# Adapter_LK-1.net
KiCad netlist of a schematic drawn in EAGLE
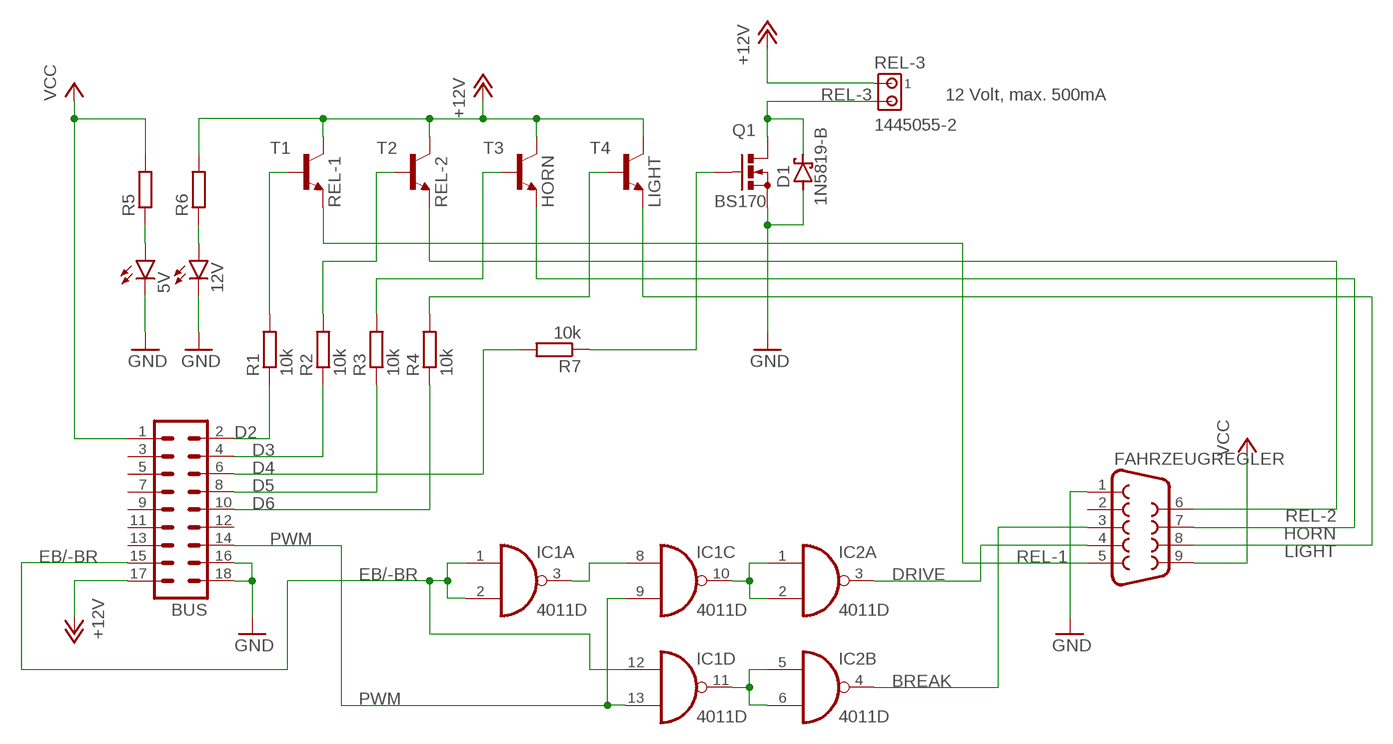
[diagram p0: schematic, sheet 1]

(export (version "E")
  (design (tool "Eeschema 10.0.6"))
  (components
    (comp (ref "5V")
      (value "LED3MM")
      (footprint "eagle-import:LED3MM")
      (libsource (lib "eagle-import") (part "LED3MM"))
    )
    (comp (ref "12V")
      (value "LED3MM")
      (footprint "eagle-import:LED3MM")
      (libsource (lib "eagle-import") (part "LED3MM"))
    )
    (comp (ref "BUS")
      (value "MA09-2")
      (footprint "eagle-import:MA09-2")
      (libsource (lib "eagle-import") (part "MA09-2"))
    )
    (comp (ref "D1")
      (value "1N5819-B")
      (footprint "eagle-import:DO41-7.6")
      (libsource (lib "eagle-import") (part "1N5819-B"))
    )
    (comp (ref "FAHRZEUGREGLER")
      (value "F09HP")
      (footprint "eagle-import:F09HP")
      (libsource (lib "eagle-import") (part "F09HP"))
    )
    (comp (ref "IC1")
      (value "4011D")
      (footprint "eagle-import:SO14")
      (libsource (lib "eagle-import") (part "4011D"))
    )
    (comp (ref "IC2")
      (value "4011D")
      (footprint "eagle-import:SO14")
      (libsource (lib "eagle-import") (part "4011D"))
    )
    (comp (ref "Q1")
      (value "BS170")
      (footprint "eagle-import:SOT54E")
      (libsource (lib "eagle-import") (part "BS170"))
    )
    (comp (ref "R1")
      (value "10k")
      (footprint "eagle-import:0204V")
      (libsource (lib "eagle-import") (part "R-EU_0204/2V"))
    )
    (comp (ref "R2")
      (value "10k")
      (footprint "eagle-import:0204V")
      (libsource (lib "eagle-import") (part "R-EU_0204/2V"))
    )
    (comp (ref "R3")
      (value "10k")
      (footprint "eagle-import:0204V")
      (libsource (lib "eagle-import") (part "R-EU_0204/2V"))
    )
    (comp (ref "R4")
      (value "10k")
      (footprint "eagle-import:0204V")
      (libsource (lib "eagle-import") (part "R-EU_0204/2V"))
    )
    (comp (ref "R5")
      (value "R-EU_0204/2V")
      (footprint "eagle-import:0204V")
      (libsource (lib "eagle-import") (part "R-EU_0204/2V"))
    )
    (comp (ref "R6")
      (value "R-EU_0204/2V")
      (footprint "eagle-import:0204V")
      (libsource (lib "eagle-import") (part "R-EU_0204/2V"))
    )
    (comp (ref "R7")
      (value "10k")
      (footprint "eagle-import:0204V")
      (libsource (lib "eagle-import") (part "R-EU_0204/2V"))
    )
    (comp (ref "REL-3")
      (value "1445055-2")
      (footprint "eagle-import:1445055-2")
      (libsource (lib "eagle-import") (part "1445055-2"))
    )
    (comp (ref "T1")
      (value "-NPN-TO92")
      (footprint "eagle-import:TO92")
      (libsource (lib "eagle-import") (part "-NPN-TO92"))
    )
    (comp (ref "T2")
      (value "-NPN-TO92")
      (footprint "eagle-import:TO92")
      (libsource (lib "eagle-import") (part "-NPN-TO92"))
    )
    (comp (ref "T3")
      (value "-NPN-TO92")
      (footprint "eagle-import:TO92")
      (libsource (lib "eagle-import") (part "-NPN-TO92"))
    )
    (comp (ref "T4")
      (value "-NPN-TO92")
      (footprint "eagle-import:TO92")
      (libsource (lib "eagle-import") (part "-NPN-TO92"))
    )
  )
  (nets
    (net (code "1") (name "+12V") (class "Default")
      (node (ref "BUS") (pin "17") (pinfunction "17_17") (pintype "passive"))
      (node (ref "R6") (pin "2") (pinfunction "2_2") (pintype "passive"))
      (node (ref "REL-3") (pin "1") (pinfunction "1_1") (pintype "passive"))
      (node (ref "T1") (pin "3") (pinfunction "C_3") (pintype "passive"))
      (node (ref "T2") (pin "3") (pinfunction "C_3") (pintype "passive"))
      (node (ref "T3") (pin "3") (pinfunction "C_3") (pintype "passive"))
      (node (ref "T4") (pin "3") (pinfunction "C_3") (pintype "passive"))
    )
    (net (code "2") (name "/BREAK") (class "Default")
      (node (ref "FAHRZEUGREGLER") (pin "3") (pinfunction "3_3") (pintype "passive"))
      (node (ref "IC2") (pin "4") (pinfunction "O_4") (pintype "output"))
    )
    (net (code "3") (name "/D2") (class "Default")
      (node (ref "BUS") (pin "2") (pinfunction "2_2") (pintype "passive"))
      (node (ref "R1") (pin "1") (pinfunction "1_1") (pintype "passive"))
    )
    (net (code "4") (name "/D3") (class "Default")
      (node (ref "BUS") (pin "4") (pinfunction "4_4") (pintype "passive"))
      (node (ref "R2") (pin "1") (pinfunction "1_1") (pintype "passive"))
    )
    (net (code "5") (name "/D4") (class "Default")
      (node (ref "BUS") (pin "6") (pinfunction "6_6") (pintype "passive"))
      (node (ref "R7") (pin "2") (pinfunction "2_2") (pintype "passive"))
    )
    (net (code "6") (name "/D5") (class "Default")
      (node (ref "BUS") (pin "8") (pinfunction "8_8") (pintype "passive"))
      (node (ref "R3") (pin "1") (pinfunction "1_1") (pintype "passive"))
    )
    (net (code "7") (name "/D6") (class "Default")
      (node (ref "BUS") (pin "10") (pinfunction "10_10") (pintype "passive"))
      (node (ref "R4") (pin "1") (pinfunction "1_1") (pintype "passive"))
    )
    (net (code "8") (name "/DRIVE") (class "Default")
      (node (ref "FAHRZEUGREGLER") (pin "4") (pinfunction "4_4") (pintype "passive"))
      (node (ref "IC2") (pin "3") (pinfunction "O_3") (pintype "output"))
    )
    (net (code "9") (name "/EB{slash}-BR") (class "Default")
      (node (ref "BUS") (pin "15") (pinfunction "15_15") (pintype "passive"))
      (node (ref "IC1") (pin "1") (pinfunction "I0_1") (pintype "input"))
      (node (ref "IC1") (pin "12") (pinfunction "I0_12") (pintype "input"))
      (node (ref "IC1") (pin "2") (pinfunction "I1_2") (pintype "input"))
    )
    (net (code "10") (name "/HORN") (class "Default")
      (node (ref "FAHRZEUGREGLER") (pin "7") (pinfunction "7_7") (pintype "passive"))
      (node (ref "T3") (pin "1") (pinfunction "E_1") (pintype "passive"))
    )
    (net (code "11") (name "/LIGHT") (class "Default")
      (node (ref "FAHRZEUGREGLER") (pin "8") (pinfunction "8_8") (pintype "passive"))
      (node (ref "T4") (pin "1") (pinfunction "E_1") (pintype "passive"))
    )
    (net (code "12") (name "/PWM") (class "Default")
      (node (ref "BUS") (pin "14") (pinfunction "14_14") (pintype "passive"))
      (node (ref "IC1") (pin "13") (pinfunction "I1_13") (pintype "input"))
      (node (ref "IC1") (pin "9") (pinfunction "I1_9") (pintype "input"))
    )
    (net (code "13") (name "/REL-1") (class "Default")
      (node (ref "FAHRZEUGREGLER") (pin "5") (pinfunction "5_5") (pintype "passive"))
      (node (ref "T1") (pin "1") (pinfunction "E_1") (pintype "passive"))
    )
    (net (code "14") (name "/REL-2") (class "Default")
      (node (ref "FAHRZEUGREGLER") (pin "6") (pinfunction "6_6") (pintype "passive"))
      (node (ref "T2") (pin "1") (pinfunction "E_1") (pintype "passive"))
    )
    (net (code "15") (name "/REL-3") (class "Default")
      (node (ref "D1") (pin "C") (pinfunction "C_C") (pintype "passive"))
      (node (ref "Q1") (pin "D") (pinfunction "D_D") (pintype "passive"))
      (node (ref "REL-3") (pin "2") (pinfunction "2_2") (pintype "passive"))
    )
    (net (code "16") (name "GND") (class "Default")
      (node (ref "12V") (pin "K") (pinfunction "C_K") (pintype "passive"))
      (node (ref "5V") (pin "K") (pinfunction "C_K") (pintype "passive"))
      (node (ref "BUS") (pin "16") (pinfunction "16_16") (pintype "passive"))
      (node (ref "BUS") (pin "18") (pinfunction "18_18") (pintype "passive"))
      (node (ref "D1") (pin "A") (pinfunction "A_A") (pintype "passive"))
      (node (ref "FAHRZEUGREGLER") (pin "1") (pinfunction "1_1") (pintype "passive"))
      (node (ref "Q1") (pin "S") (pinfunction "S_S") (pintype "passive"))
    )
    (net (code "17") (name "Net-(5V-PadA)") (class "Default")
      (node (ref "5V") (pin "A") (pinfunction "A_A") (pintype "passive"))
      (node (ref "R5") (pin "1") (pinfunction "1_1") (pintype "passive"))
    )
    (net (code "18") (name "Net-(12V-PadA)") (class "Default")
      (node (ref "12V") (pin "A") (pinfunction "A_A") (pintype "passive"))
      (node (ref "R6") (pin "1") (pinfunction "1_1") (pintype "passive"))
    )
    (net (code "19") (name "Net-(IC1A-O)") (class "Default")
      (node (ref "IC1") (pin "3") (pinfunction "O_3") (pintype "output"))
      (node (ref "IC1") (pin "8") (pinfunction "I0_8") (pintype "input"))
    )
    (net (code "20") (name "Net-(IC1C-O)") (class "Default")
      (node (ref "IC1") (pin "10") (pinfunction "O_10") (pintype "output"))
      (node (ref "IC2") (pin "1") (pinfunction "I0_1") (pintype "input"))
      (node (ref "IC2") (pin "2") (pinfunction "I1_2") (pintype "input"))
    )
    (net (code "21") (name "Net-(IC1D-O)") (class "Default")
      (node (ref "IC1") (pin "11") (pinfunction "O_11") (pintype "output"))
      (node (ref "IC2") (pin "5") (pinfunction "I0_5") (pintype "input"))
      (node (ref "IC2") (pin "6") (pinfunction "I1_6") (pintype "input"))
    )
    (net (code "22") (name "Net-(Q1-PadG)") (class "Default")
      (node (ref "Q1") (pin "G") (pinfunction "G_G") (pintype "passive"))
      (node (ref "R7") (pin "1") (pinfunction "1_1") (pintype "passive"))
    )
    (net (code "23") (name "Net-(T1-B)") (class "Default")
      (node (ref "R1") (pin "2") (pinfunction "2_2") (pintype "passive"))
      (node (ref "T1") (pin "2") (pinfunction "B_2") (pintype "passive"))
    )
    (net (code "24") (name "Net-(T2-B)") (class "Default")
      (node (ref "R2") (pin "2") (pinfunction "2_2") (pintype "passive"))
      (node (ref "T2") (pin "2") (pinfunction "B_2") (pintype "passive"))
    )
    (net (code "25") (name "Net-(T3-B)") (class "Default")
      (node (ref "R3") (pin "2") (pinfunction "2_2") (pintype "passive"))
      (node (ref "T3") (pin "2") (pinfunction "B_2") (pintype "passive"))
    )
    (net (code "26") (name "Net-(T4-B)") (class "Default")
      (node (ref "R4") (pin "2") (pinfunction "2_2") (pintype "passive"))
      (node (ref "T4") (pin "2") (pinfunction "B_2") (pintype "passive"))
    )
    (net (code "27") (name "VCC") (class "Default")
      (node (ref "BUS") (pin "1") (pinfunction "1_1") (pintype "passive"))
      (node (ref "FAHRZEUGREGLER") (pin "9") (pinfunction "9_9") (pintype "passive"))
      (node (ref "R5") (pin "2") (pinfunction "2_2") (pintype "passive"))
    )
    (net (code "28") (name "unconnected-(BUS-Pad3)") (class "Default")
      (node (ref "BUS") (pin "3") (pinfunction "3_3") (pintype "passive"))
    )
    (net (code "29") (name "unconnected-(BUS-Pad5)") (class "Default")
      (node (ref "BUS") (pin "5") (pinfunction "5_5") (pintype "passive"))
    )
    (net (code "30") (name "unconnected-(BUS-Pad7)") (class "Default")
      (node (ref "BUS") (pin "7") (pinfunction "7_7") (pintype "passive"))
    )
    (net (code "31") (name "unconnected-(BUS-Pad9)") (class "Default")
      (node (ref "BUS") (pin "9") (pinfunction "9_9") (pintype "passive"))
    )
    (net (code "32") (name "unconnected-(BUS-Pad11)") (class "Default")
      (node (ref "BUS") (pin "11") (pinfunction "11_11") (pintype "passive"))
    )
    (net (code "33") (name "unconnected-(BUS-Pad12)") (class "Default")
      (node (ref "BUS") (pin "12") (pinfunction "12_12") (pintype "passive"))
    )
    (net (code "34") (name "unconnected-(BUS-Pad13)") (class "Default")
      (node (ref "BUS") (pin "13") (pinfunction "13_13") (pintype "passive"))
    )
    (net (code "35") (name "unconnected-(FAHRZEUGREGLER-Pad2)") (class "Default")
      (node (ref "FAHRZEUGREGLER") (pin "2") (pinfunction "2_2") (pintype "passive"))
    )
  )
)
